# ledpower.net
KiCad netlist of a schematic drawn in EAGLE
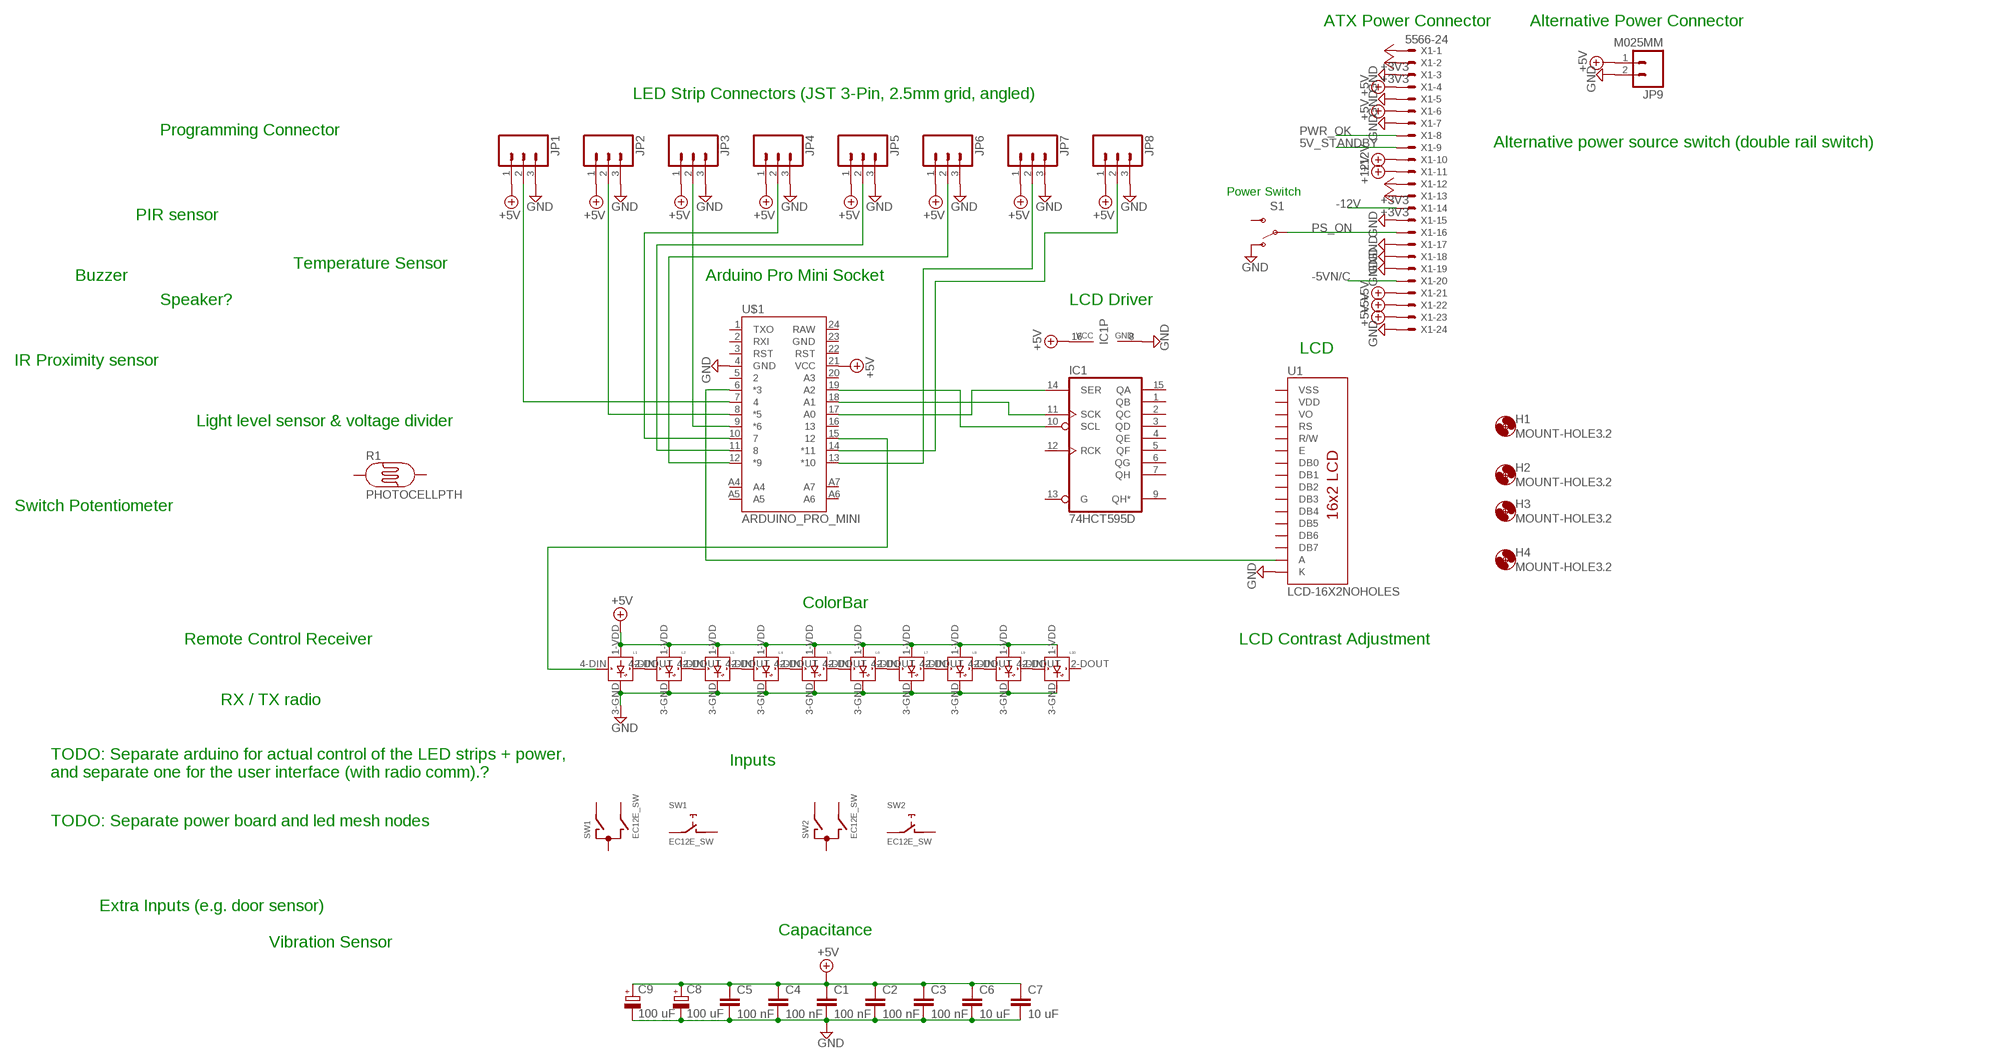
[diagram p0: schematic, sheet 1]

(export (version "E")
  (design (tool "Eeschema 10.0.6"))
  (components
    (comp (ref "C1")
      (value "100 nF")
      (footprint "eagle-import:C0805")
      (libsource (lib "eagle-import") (part "C-EUC0805"))
    )
    (comp (ref "C2")
      (value "100 nF")
      (footprint "eagle-import:C0805")
      (libsource (lib "eagle-import") (part "C-EUC0805"))
    )
    (comp (ref "C3")
      (value "100 nF")
      (footprint "eagle-import:C0805")
      (libsource (lib "eagle-import") (part "C-EUC0805"))
    )
    (comp (ref "C4")
      (value "100 nF")
      (footprint "eagle-import:C0805")
      (libsource (lib "eagle-import") (part "C-EUC0805"))
    )
    (comp (ref "C5")
      (value "100 nF")
      (footprint "eagle-import:C0805")
      (libsource (lib "eagle-import") (part "C-EUC0805"))
    )
    (comp (ref "C6")
      (value "10 uF")
      (footprint "eagle-import:C1206")
      (libsource (lib "eagle-import") (part "C-EUC1206"))
    )
    (comp (ref "C7")
      (value "10 uF")
      (footprint "eagle-import:C1206")
      (libsource (lib "eagle-import") (part "C-EUC1206"))
    )
    (comp (ref "C8")
      (value "100 uF")
      (footprint "eagle-import:E3,5-10")
      (libsource (lib "eagle-import") (part "CPOL-EUE3.5-10"))
    )
    (comp (ref "C9")
      (value "100 uF")
      (footprint "eagle-import:E3,5-10")
      (libsource (lib "eagle-import") (part "CPOL-EUE3.5-10"))
    )
    (comp (ref "H1")
      (value "MOUNT-HOLE3.2")
      (footprint "eagle-import:3,2")
      (libsource (lib "eagle-import") (part "MOUNT-HOLE3.2"))
    )
    (comp (ref "H2")
      (value "MOUNT-HOLE3.2")
      (footprint "eagle-import:3,2")
      (libsource (lib "eagle-import") (part "MOUNT-HOLE3.2"))
    )
    (comp (ref "H3")
      (value "MOUNT-HOLE3.2")
      (footprint "eagle-import:3,2")
      (libsource (lib "eagle-import") (part "MOUNT-HOLE3.2"))
    )
    (comp (ref "H4")
      (value "MOUNT-HOLE3.2")
      (footprint "eagle-import:3,2")
      (libsource (lib "eagle-import") (part "MOUNT-HOLE3.2"))
    )
    (comp (ref "IC1")
      (value "74HCT595D")
      (footprint "eagle-import:SO16")
      (libsource (lib "eagle-import") (part "74595DHCT"))
    )
    (comp (ref "JP1")
      (value "M03LONGPADS")
      (footprint "eagle-import:1X03_LONGPADS")
      (libsource (lib "eagle-import") (part "M03LONGPADS"))
    )
    (comp (ref "JP2")
      (value "M03LONGPADS")
      (footprint "eagle-import:1X03_LONGPADS")
      (libsource (lib "eagle-import") (part "M03LONGPADS"))
    )
    (comp (ref "JP3")
      (value "M03LONGPADS")
      (footprint "eagle-import:1X03_LONGPADS")
      (libsource (lib "eagle-import") (part "M03LONGPADS"))
    )
    (comp (ref "JP4")
      (value "M03LONGPADS")
      (footprint "eagle-import:1X03_LONGPADS")
      (libsource (lib "eagle-import") (part "M03LONGPADS"))
    )
    (comp (ref "JP5")
      (value "M03LONGPADS")
      (footprint "eagle-import:1X03_LONGPADS")
      (libsource (lib "eagle-import") (part "M03LONGPADS"))
    )
    (comp (ref "JP6")
      (value "M03LONGPADS")
      (footprint "eagle-import:1X03_LONGPADS")
      (libsource (lib "eagle-import") (part "M03LONGPADS"))
    )
    (comp (ref "JP7")
      (value "M03LONGPADS")
      (footprint "eagle-import:1X03_LONGPADS")
      (libsource (lib "eagle-import") (part "M03LONGPADS"))
    )
    (comp (ref "JP8")
      (value "M03LONGPADS")
      (footprint "eagle-import:1X03_LONGPADS")
      (libsource (lib "eagle-import") (part "M03LONGPADS"))
    )
    (comp (ref "JP9")
      (value "M025MM")
      (footprint "eagle-import:SCREWTERMINAL-5MM-2")
      (libsource (lib "eagle-import") (part "M025MM"))
    )
    (comp (ref "L1")
      (value "WS2812B")
      (footprint "eagle-import:WS2812B")
      (libsource (lib "eagle-import") (part "WS2812B"))
    )
    (comp (ref "L2")
      (value "WS2812B")
      (footprint "eagle-import:WS2812B")
      (libsource (lib "eagle-import") (part "WS2812B"))
    )
    (comp (ref "L3")
      (value "WS2812B")
      (footprint "eagle-import:WS2812B")
      (libsource (lib "eagle-import") (part "WS2812B"))
    )
    (comp (ref "L4")
      (value "WS2812B")
      (footprint "eagle-import:WS2812B")
      (libsource (lib "eagle-import") (part "WS2812B"))
    )
    (comp (ref "L5")
      (value "WS2812B")
      (footprint "eagle-import:WS2812B")
      (libsource (lib "eagle-import") (part "WS2812B"))
    )
    (comp (ref "L6")
      (value "WS2812B")
      (footprint "eagle-import:WS2812B")
      (libsource (lib "eagle-import") (part "WS2812B"))
    )
    (comp (ref "L7")
      (value "WS2812B")
      (footprint "eagle-import:WS2812B")
      (libsource (lib "eagle-import") (part "WS2812B"))
    )
    (comp (ref "L8")
      (value "WS2812B")
      (footprint "eagle-import:WS2812B")
      (libsource (lib "eagle-import") (part "WS2812B"))
    )
    (comp (ref "L9")
      (value "WS2812B")
      (footprint "eagle-import:WS2812B")
      (libsource (lib "eagle-import") (part "WS2812B"))
    )
    (comp (ref "L10")
      (value "WS2812B")
      (footprint "eagle-import:WS2812B")
      (libsource (lib "eagle-import") (part "WS2812B"))
    )
    (comp (ref "R1")
      (value "PHOTOCELLPTH")
      (footprint "eagle-import:PHOTOCELL")
      (libsource (lib "eagle-import") (part "PHOTOCELLPTH"))
    )
    (comp (ref "S1")
      (value "SWITCH-SPSTPTH")
      (footprint "eagle-import:SWITCH-SPDT")
      (libsource (lib "eagle-import") (part "SWITCH-SPSTPTH"))
    )
    (comp (ref "SW1")
      (value "EC12E_SW")
      (footprint "eagle-import:ALPS_EC12E_SW")
      (fields (field (name "MPN") "EC12E2424407"))
      (libsource (lib "eagle-import") (part "EC12E_SW"))
    )
    (comp (ref "SW2")
      (value "EC12E_SW")
      (footprint "eagle-import:ALPS_EC12E_SW")
      (fields (field (name "MPN") "EC12E2424407"))
      (libsource (lib "eagle-import") (part "EC12E_SW"))
    )
    (comp (ref "U$1")
      (value "ARDUINO_PRO_MINI")
      (footprint "eagle-import:ARDUINO_PRO_MINI")
      (libsource (lib "eagle-import") (part "ARDUINO_PRO_MINI"))
    )
    (comp (ref "U1")
      (value "LCD-16X2NOHOLES")
      (footprint "eagle-import:LCD-16X2_NOHOLES")
      (libsource (lib "eagle-import") (part "LCD-16X2NOHOLES"))
    )
    (comp (ref "X1")
      (value "5566-24")
      (footprint "eagle-import:5566-24")
      (libsource (lib "eagle-import") (part "5566-24"))
    )
  )
  (nets
    (net (code "1") (name "+3V3") (class "Default")
      (node (ref "X1") (pin "1") (pinfunction "S_1") (pintype "passive"))
      (node (ref "X1") (pin "12") (pinfunction "S_12") (pintype "passive"))
      (node (ref "X1") (pin "13") (pinfunction "S_13") (pintype "passive"))
      (node (ref "X1") (pin "2") (pinfunction "S_2") (pintype "passive"))
    )
    (net (code "2") (name "+5V") (class "Default")
      (node (ref "C1") (pin "1") (pinfunction "1_1") (pintype "passive"))
      (node (ref "C2") (pin "1") (pinfunction "1_1") (pintype "passive"))
      (node (ref "C3") (pin "1") (pinfunction "1_1") (pintype "passive"))
      (node (ref "C4") (pin "1") (pinfunction "1_1") (pintype "passive"))
      (node (ref "C5") (pin "1") (pinfunction "1_1") (pintype "passive"))
      (node (ref "C6") (pin "1") (pinfunction "1_1") (pintype "passive"))
      (node (ref "C7") (pin "1") (pinfunction "1_1") (pintype "passive"))
      (node (ref "C8") (pin "+") (pinfunction "+_+") (pintype "passive"))
      (node (ref "C9") (pin "+") (pinfunction "+_+") (pintype "passive"))
      (node (ref "IC1") (pin "16") (pinfunction "VCC_16") (pintype "power_in"))
      (node (ref "JP1") (pin "1") (pinfunction "1_1") (pintype "passive"))
      (node (ref "JP2") (pin "1") (pinfunction "1_1") (pintype "passive"))
      (node (ref "JP3") (pin "1") (pinfunction "1_1") (pintype "passive"))
      (node (ref "JP4") (pin "1") (pinfunction "1_1") (pintype "passive"))
      (node (ref "JP5") (pin "1") (pinfunction "1_1") (pintype "passive"))
      (node (ref "JP6") (pin "1") (pinfunction "1_1") (pintype "passive"))
      (node (ref "JP7") (pin "1") (pinfunction "1_1") (pintype "passive"))
      (node (ref "JP8") (pin "1") (pinfunction "1_1") (pintype "passive"))
      (node (ref "JP9") (pin "1") (pinfunction "1_1") (pintype "passive"))
      (node (ref "L1") (pin "1-VDD") (pinfunction "VDD_1-VDD") (pintype "bidirectional"))
      (node (ref "L10") (pin "1-VDD") (pinfunction "VDD_1-VDD") (pintype "bidirectional"))
      (node (ref "L2") (pin "1-VDD") (pinfunction "VDD_1-VDD") (pintype "bidirectional"))
      (node (ref "L3") (pin "1-VDD") (pinfunction "VDD_1-VDD") (pintype "bidirectional"))
      (node (ref "L4") (pin "1-VDD") (pinfunction "VDD_1-VDD") (pintype "bidirectional"))
      (node (ref "L5") (pin "1-VDD") (pinfunction "VDD_1-VDD") (pintype "bidirectional"))
      (node (ref "L6") (pin "1-VDD") (pinfunction "VDD_1-VDD") (pintype "bidirectional"))
      (node (ref "L7") (pin "1-VDD") (pinfunction "VDD_1-VDD") (pintype "bidirectional"))
      (node (ref "L8") (pin "1-VDD") (pinfunction "VDD_1-VDD") (pintype "bidirectional"))
      (node (ref "L9") (pin "1-VDD") (pinfunction "VDD_1-VDD") (pintype "bidirectional"))
      (node (ref "U$1") (pin "21") (pinfunction "VCC_21") (pintype "bidirectional"))
      (node (ref "X1") (pin "21") (pinfunction "S_21") (pintype "passive"))
      (node (ref "X1") (pin "22") (pinfunction "S_22") (pintype "passive"))
      (node (ref "X1") (pin "23") (pinfunction "S_23") (pintype "passive"))
      (node (ref "X1") (pin "4") (pinfunction "S_4") (pintype "passive"))
      (node (ref "X1") (pin "6") (pinfunction "S_6") (pintype "passive"))
    )
    (net (code "3") (name "+12V") (class "Default")
      (node (ref "X1") (pin "10") (pinfunction "S_10") (pintype "passive"))
      (node (ref "X1") (pin "11") (pinfunction "S_11") (pintype "passive"))
    )
    (net (code "4") (name "/-5VN{slash}C") (class "Default")
      (node (ref "X1") (pin "20") (pinfunction "S_20") (pintype "passive"))
    )
    (net (code "5") (name "/-12V") (class "Default")
      (node (ref "X1") (pin "14") (pinfunction "S_14") (pintype "passive"))
    )
    (net (code "6") (name "/5V_STANDBY") (class "Default")
      (node (ref "X1") (pin "9") (pinfunction "S_9") (pintype "passive"))
    )
    (net (code "7") (name "/PS_ON") (class "Default")
      (node (ref "S1") (pin "2") (pinfunction "P_2") (pintype "passive"))
      (node (ref "X1") (pin "16") (pinfunction "S_16") (pintype "passive"))
    )
    (net (code "8") (name "/PWR_OK") (class "Default")
      (node (ref "X1") (pin "8") (pinfunction "S_8") (pintype "passive"))
    )
    (net (code "9") (name "/VDD") (class "Default")
      (node (ref "U1") (pin "2") (pinfunction "VDD_2") (pintype "power_in"))
    )
    (net (code "10") (name "/VSS") (class "Default")
      (node (ref "U1") (pin "1") (pinfunction "VSS_1") (pintype "power_in"))
    )
    (net (code "11") (name "GND") (class "Default")
      (node (ref "C1") (pin "2") (pinfunction "2_2") (pintype "passive"))
      (node (ref "C2") (pin "2") (pinfunction "2_2") (pintype "passive"))
      (node (ref "C3") (pin "2") (pinfunction "2_2") (pintype "passive"))
      (node (ref "C4") (pin "2") (pinfunction "2_2") (pintype "passive"))
      (node (ref "C5") (pin "2") (pinfunction "2_2") (pintype "passive"))
      (node (ref "C6") (pin "2") (pinfunction "2_2") (pintype "passive"))
      (node (ref "C7") (pin "2") (pinfunction "2_2") (pintype "passive"))
      (node (ref "C8") (pin "-") (pinfunction "-_-") (pintype "passive"))
      (node (ref "C9") (pin "-") (pinfunction "-_-") (pintype "passive"))
      (node (ref "IC1") (pin "8") (pinfunction "GND_8") (pintype "power_in"))
      (node (ref "JP1") (pin "3") (pinfunction "3_3") (pintype "passive"))
      (node (ref "JP2") (pin "3") (pinfunction "3_3") (pintype "passive"))
      (node (ref "JP3") (pin "3") (pinfunction "3_3") (pintype "passive"))
      (node (ref "JP4") (pin "3") (pinfunction "3_3") (pintype "passive"))
      (node (ref "JP5") (pin "3") (pinfunction "3_3") (pintype "passive"))
      (node (ref "JP6") (pin "3") (pinfunction "3_3") (pintype "passive"))
      (node (ref "JP7") (pin "3") (pinfunction "3_3") (pintype "passive"))
      (node (ref "JP8") (pin "3") (pinfunction "3_3") (pintype "passive"))
      (node (ref "JP9") (pin "2") (pinfunction "2_2") (pintype "passive"))
      (node (ref "L1") (pin "3-GND") (pinfunction "GND_3-GND") (pintype "bidirectional"))
      (node (ref "L10") (pin "3-GND") (pinfunction "GND_3-GND") (pintype "bidirectional"))
      (node (ref "L2") (pin "3-GND") (pinfunction "GND_3-GND") (pintype "bidirectional"))
      (node (ref "L3") (pin "3-GND") (pinfunction "GND_3-GND") (pintype "bidirectional"))
      (node (ref "L4") (pin "3-GND") (pinfunction "GND_3-GND") (pintype "bidirectional"))
      (node (ref "L5") (pin "3-GND") (pinfunction "GND_3-GND") (pintype "bidirectional"))
      (node (ref "L6") (pin "3-GND") (pinfunction "GND_3-GND") (pintype "bidirectional"))
      (node (ref "L7") (pin "3-GND") (pinfunction "GND_3-GND") (pintype "bidirectional"))
      (node (ref "L8") (pin "3-GND") (pinfunction "GND_3-GND") (pintype "bidirectional"))
      (node (ref "L9") (pin "3-GND") (pinfunction "GND_3-GND") (pintype "bidirectional"))
      (node (ref "S1") (pin "1") (pinfunction "O_1") (pintype "passive"))
      (node (ref "U$1") (pin "4") (pinfunction "GND_4") (pintype "bidirectional"))
      (node (ref "U1") (pin "16") (pinfunction "K_16") (pintype "power_in"))
      (node (ref "X1") (pin "15") (pinfunction "S_15") (pintype "passive"))
      (node (ref "X1") (pin "17") (pinfunction "S_17") (pintype "passive"))
      (node (ref "X1") (pin "18") (pinfunction "S_18") (pintype "passive"))
      (node (ref "X1") (pin "19") (pinfunction "S_19") (pintype "passive"))
      (node (ref "X1") (pin "24") (pinfunction "S_24") (pintype "passive"))
      (node (ref "X1") (pin "3") (pinfunction "S_3") (pintype "passive"))
      (node (ref "X1") (pin "5") (pinfunction "S_5") (pintype "passive"))
      (node (ref "X1") (pin "7") (pinfunction "S_7") (pintype "passive"))
    )
    (net (code "12") (name "Net-(IC1A-SCK)") (class "Default")
      (node (ref "IC1") (pin "11") (pinfunction "SCK_11") (pintype "input"))
      (node (ref "U$1") (pin "18") (pinfunction "A1_18") (pintype "bidirectional"))
    )
    (net (code "13") (name "Net-(IC1A-SCL)") (class "Default")
      (node (ref "IC1") (pin "10") (pinfunction "SCL_10") (pintype "input"))
      (node (ref "U$1") (pin "19") (pinfunction "A2_19") (pintype "bidirectional"))
    )
    (net (code "14") (name "Net-(IC1A-SER)") (class "Default")
      (node (ref "IC1") (pin "14") (pinfunction "SER_14") (pintype "input"))
      (node (ref "U$1") (pin "17") (pinfunction "A0_17") (pintype "bidirectional"))
    )
    (net (code "15") (name "Net-(L1-DIN)") (class "Default")
      (node (ref "L1") (pin "4-DIN") (pinfunction "DIN_4-DIN") (pintype "input"))
      (node (ref "U$1") (pin "15") (pinfunction "12_15") (pintype "bidirectional"))
    )
    (net (code "16") (name "Net-(L1-DOUT)") (class "Default")
      (node (ref "L1") (pin "2-DOUT") (pinfunction "DOUT_2-DOUT") (pintype "output"))
      (node (ref "L2") (pin "4-DIN") (pinfunction "DIN_4-DIN") (pintype "input"))
    )
    (net (code "17") (name "Net-(L2-DOUT)") (class "Default")
      (node (ref "L2") (pin "2-DOUT") (pinfunction "DOUT_2-DOUT") (pintype "output"))
      (node (ref "L3") (pin "4-DIN") (pinfunction "DIN_4-DIN") (pintype "input"))
    )
    (net (code "18") (name "Net-(L3-DOUT)") (class "Default")
      (node (ref "L3") (pin "2-DOUT") (pinfunction "DOUT_2-DOUT") (pintype "output"))
      (node (ref "L4") (pin "4-DIN") (pinfunction "DIN_4-DIN") (pintype "input"))
    )
    (net (code "19") (name "Net-(L4-DOUT)") (class "Default")
      (node (ref "L4") (pin "2-DOUT") (pinfunction "DOUT_2-DOUT") (pintype "output"))
      (node (ref "L5") (pin "4-DIN") (pinfunction "DIN_4-DIN") (pintype "input"))
    )
    (net (code "20") (name "Net-(L5-DOUT)") (class "Default")
      (node (ref "L5") (pin "2-DOUT") (pinfunction "DOUT_2-DOUT") (pintype "output"))
      (node (ref "L6") (pin "4-DIN") (pinfunction "DIN_4-DIN") (pintype "input"))
    )
    (net (code "21") (name "Net-(L6-DOUT)") (class "Default")
      (node (ref "L6") (pin "2-DOUT") (pinfunction "DOUT_2-DOUT") (pintype "output"))
      (node (ref "L7") (pin "4-DIN") (pinfunction "DIN_4-DIN") (pintype "input"))
    )
    (net (code "22") (name "Net-(L7-DOUT)") (class "Default")
      (node (ref "L7") (pin "2-DOUT") (pinfunction "DOUT_2-DOUT") (pintype "output"))
      (node (ref "L8") (pin "4-DIN") (pinfunction "DIN_4-DIN") (pintype "input"))
    )
    (net (code "23") (name "Net-(L8-DOUT)") (class "Default")
      (node (ref "L8") (pin "2-DOUT") (pinfunction "DOUT_2-DOUT") (pintype "output"))
      (node (ref "L9") (pin "4-DIN") (pinfunction "DIN_4-DIN") (pintype "input"))
    )
    (net (code "24") (name "Net-(L10-DIN)") (class "Default")
      (node (ref "L10") (pin "4-DIN") (pinfunction "DIN_4-DIN") (pintype "input"))
      (node (ref "L9") (pin "2-DOUT") (pinfunction "DOUT_2-DOUT") (pintype "output"))
    )
    (net (code "25") (name "Net-(U$1-*3)") (class "Default")
      (node (ref "U$1") (pin "6") (pinfunction "*3_6") (pintype "bidirectional"))
      (node (ref "U1") (pin "15") (pinfunction "A_15") (pintype "power_in"))
    )
    (net (code "26") (name "Net-(U$1-*5)") (class "Default")
      (node (ref "JP2") (pin "2") (pinfunction "2_2") (pintype "passive"))
      (node (ref "U$1") (pin "8") (pinfunction "*5_8") (pintype "bidirectional"))
    )
    (net (code "27") (name "Net-(U$1-*6)") (class "Default")
      (node (ref "JP3") (pin "2") (pinfunction "2_2") (pintype "passive"))
      (node (ref "U$1") (pin "9") (pinfunction "*6_9") (pintype "bidirectional"))
    )
    (net (code "28") (name "Net-(U$1-*9)") (class "Default")
      (node (ref "JP6") (pin "2") (pinfunction "2_2") (pintype "passive"))
      (node (ref "U$1") (pin "12") (pinfunction "*9_12") (pintype "bidirectional"))
    )
    (net (code "29") (name "Net-(U$1-*10)") (class "Default")
      (node (ref "JP7") (pin "2") (pinfunction "2_2") (pintype "passive"))
      (node (ref "U$1") (pin "13") (pinfunction "*10_13") (pintype "bidirectional"))
    )
    (net (code "30") (name "Net-(U$1-*11)") (class "Default")
      (node (ref "JP8") (pin "2") (pinfunction "2_2") (pintype "passive"))
      (node (ref "U$1") (pin "14") (pinfunction "*11_14") (pintype "bidirectional"))
    )
    (net (code "31") (name "Net-(U$1-4)") (class "Default")
      (node (ref "JP1") (pin "2") (pinfunction "2_2") (pintype "passive"))
      (node (ref "U$1") (pin "7") (pinfunction "4_7") (pintype "bidirectional"))
    )
    (net (code "32") (name "Net-(U$1-7)") (class "Default")
      (node (ref "JP4") (pin "2") (pinfunction "2_2") (pintype "passive"))
      (node (ref "U$1") (pin "10") (pinfunction "7_10") (pintype "bidirectional"))
    )
    (net (code "33") (name "Net-(U$1-8)") (class "Default")
      (node (ref "JP5") (pin "2") (pinfunction "2_2") (pintype "passive"))
      (node (ref "U$1") (pin "11") (pinfunction "8_11") (pintype "bidirectional"))
    )
    (net (code "34") (name "unconnected-(IC1A-G-Pad13)") (class "Default")
      (node (ref "IC1") (pin "13") (pinfunction "G_13") (pintype "input"))
    )
    (net (code "35") (name "unconnected-(IC1A-QA-Pad15)") (class "Default")
      (node (ref "IC1") (pin "15") (pinfunction "QA_15") (pintype "tri_state"))
    )
    (net (code "36") (name "unconnected-(IC1A-QB-Pad1)") (class "Default")
      (node (ref "IC1") (pin "1") (pinfunction "QB_1") (pintype "tri_state"))
    )
    (net (code "37") (name "unconnected-(IC1A-QC-Pad2)") (class "Default")
      (node (ref "IC1") (pin "2") (pinfunction "QC_2") (pintype "tri_state"))
    )
    (net (code "38") (name "unconnected-(IC1A-QD-Pad3)") (class "Default")
      (node (ref "IC1") (pin "3") (pinfunction "QD_3") (pintype "tri_state"))
    )
    (net (code "39") (name "unconnected-(IC1A-QE-Pad4)") (class "Default")
      (node (ref "IC1") (pin "4") (pinfunction "QE_4") (pintype "tri_state"))
    )
    (net (code "40") (name "unconnected-(IC1A-QF-Pad5)") (class "Default")
      (node (ref "IC1") (pin "5") (pinfunction "QF_5") (pintype "tri_state"))
    )
    (net (code "41") (name "unconnected-(IC1A-QG-Pad6)") (class "Default")
      (node (ref "IC1") (pin "6") (pinfunction "QG_6") (pintype "tri_state"))
    )
    (net (code "42") (name "unconnected-(IC1A-QH*-Pad9)") (class "Default")
      (node (ref "IC1") (pin "9") (pinfunction "QH*_9") (pintype "tri_state"))
    )
    (net (code "43") (name "unconnected-(IC1A-QH-Pad7)") (class "Default")
      (node (ref "IC1") (pin "7") (pinfunction "QH_7") (pintype "tri_state"))
    )
    (net (code "44") (name "unconnected-(IC1A-RCK-Pad12)") (class "Default")
      (node (ref "IC1") (pin "12") (pinfunction "RCK_12") (pintype "input"))
    )
    (net (code "45") (name "unconnected-(L10-DOUT-Pad2-DOUT)") (class "Default")
      (node (ref "L10") (pin "2-DOUT") (pinfunction "DOUT_2-DOUT") (pintype "output"))
    )
    (net (code "46") (name "unconnected-(R1-P$1-Pad1)") (class "Default")
      (node (ref "R1") (pin "1") (pinfunction "P$1_1") (pintype "bidirectional"))
    )
    (net (code "47") (name "unconnected-(R1-P$2-Pad2)") (class "Default")
      (node (ref "R1") (pin "2") (pinfunction "P$2_2") (pintype "bidirectional"))
    )
    (net (code "48") (name "unconnected-(S1-S-Pad3)") (class "Default")
      (node (ref "S1") (pin "3") (pinfunction "S_3") (pintype "passive"))
    )
    (net (code "49") (name "unconnected-(SW1-PadA)") (class "Default")
      (node (ref "SW1") (pin "A") (pinfunction "A_A") (pintype "passive"))
    )
    (net (code "50") (name "unconnected-(SW1-PadB)") (class "Default")
      (node (ref "SW1") (pin "B") (pinfunction "B_B") (pintype "passive"))
    )
    (net (code "51") (name "unconnected-(SW1-PadC)") (class "Default")
      (node (ref "SW1") (pin "C") (pinfunction "C_C") (pintype "passive"))
    )
    (net (code "52") (name "unconnected-(SW1B-1-PadD)") (class "Default")
      (node (ref "SW1") (pin "D") (pinfunction "1_D") (pintype "passive"))
    )
    (net (code "53") (name "unconnected-(SW1B-2-PadE)") (class "Default")
      (node (ref "SW1") (pin "E") (pinfunction "2_E") (pintype "passive"))
    )
    (net (code "54") (name "unconnected-(SW2-PadA)") (class "Default")
      (node (ref "SW2") (pin "A") (pinfunction "A_A") (pintype "passive"))
    )
    (net (code "55") (name "unconnected-(SW2-PadB)") (class "Default")
      (node (ref "SW2") (pin "B") (pinfunction "B_B") (pintype "passive"))
    )
    (net (code "56") (name "unconnected-(SW2-PadC)") (class "Default")
      (node (ref "SW2") (pin "C") (pinfunction "C_C") (pintype "passive"))
    )
    (net (code "57") (name "unconnected-(SW2B-1-PadD)") (class "Default")
      (node (ref "SW2") (pin "D") (pinfunction "1_D") (pintype "passive"))
    )
    (net (code "58") (name "unconnected-(SW2B-2-PadE)") (class "Default")
      (node (ref "SW2") (pin "E") (pinfunction "2_E") (pintype "passive"))
    )
    (net (code "59") (name "unconnected-(U$1-2-Pad5)") (class "Default")
      (node (ref "U$1") (pin "5") (pinfunction "2_5") (pintype "bidirectional"))
    )
    (net (code "60") (name "unconnected-(U$1-13-Pad16)") (class "Default")
      (node (ref "U$1") (pin "16") (pinfunction "13_16") (pintype "bidirectional"))
    )
    (net (code "61") (name "unconnected-(U$1-A3-Pad20)") (class "Default")
      (node (ref "U$1") (pin "20") (pinfunction "A3_20") (pintype "bidirectional"))
    )
    (net (code "62") (name "unconnected-(U$1-GND-Pad23)") (class "Default")
      (node (ref "U$1") (pin "23") (pinfunction "GND_23") (pintype "bidirectional"))
    )
    (net (code "63") (name "unconnected-(U$1-PadA4)") (class "Default")
      (node (ref "U$1") (pin "A4") (pinfunction "A4_A4") (pintype "bidirectional"))
    )
    (net (code "64") (name "unconnected-(U$1-PadA5)") (class "Default")
      (node (ref "U$1") (pin "A5") (pinfunction "A5_A5") (pintype "bidirectional"))
    )
    (net (code "65") (name "unconnected-(U$1-PadA6)") (class "Default")
      (node (ref "U$1") (pin "A6") (pinfunction "A6_A6") (pintype "bidirectional"))
    )
    (net (code "66") (name "unconnected-(U$1-PadA7)") (class "Default")
      (node (ref "U$1") (pin "A7") (pinfunction "A7_A7") (pintype "bidirectional"))
    )
    (net (code "67") (name "unconnected-(U$1-RAW-Pad24)") (class "Default")
      (node (ref "U$1") (pin "24") (pinfunction "RAW_24") (pintype "bidirectional"))
    )
    (net (code "68") (name "unconnected-(U$1-RST-Pad3)") (class "Default")
      (node (ref "U$1") (pin "3") (pinfunction "RST_3") (pintype "bidirectional"))
    )
    (net (code "69") (name "unconnected-(U$1-RST-Pad22)") (class "Default")
      (node (ref "U$1") (pin "22") (pinfunction "RST_22") (pintype "bidirectional"))
    )
    (net (code "70") (name "unconnected-(U$1-RXI-Pad2)") (class "Default")
      (node (ref "U$1") (pin "2") (pinfunction "RXI_2") (pintype "bidirectional"))
    )
    (net (code "71") (name "unconnected-(U$1-TXO-Pad1)") (class "Default")
      (node (ref "U$1") (pin "1") (pinfunction "TXO_1") (pintype "bidirectional"))
    )
    (net (code "72") (name "unconnected-(U1-DB0-Pad7)") (class "Default")
      (node (ref "U1") (pin "7") (pinfunction "DB0_7") (pintype "bidirectional"))
    )
    (net (code "73") (name "unconnected-(U1-DB1-Pad8)") (class "Default")
      (node (ref "U1") (pin "8") (pinfunction "DB1_8") (pintype "bidirectional"))
    )
    (net (code "74") (name "unconnected-(U1-DB2-Pad9)") (class "Default")
      (node (ref "U1") (pin "9") (pinfunction "DB2_9") (pintype "bidirectional"))
    )
    (net (code "75") (name "unconnected-(U1-DB3-Pad10)") (class "Default")
      (node (ref "U1") (pin "10") (pinfunction "DB3_10") (pintype "bidirectional"))
    )
    (net (code "76") (name "unconnected-(U1-DB4-Pad11)") (class "Default")
      (node (ref "U1") (pin "11") (pinfunction "DB4_11") (pintype "bidirectional"))
    )
    (net (code "77") (name "unconnected-(U1-DB5-Pad12)") (class "Default")
      (node (ref "U1") (pin "12") (pinfunction "DB5_12") (pintype "bidirectional"))
    )
    (net (code "78") (name "unconnected-(U1-DB6-Pad13)") (class "Default")
      (node (ref "U1") (pin "13") (pinfunction "DB6_13") (pintype "bidirectional"))
    )
    (net (code "79") (name "unconnected-(U1-DB7-Pad14)") (class "Default")
      (node (ref "U1") (pin "14") (pinfunction "DB7_14") (pintype "bidirectional"))
    )
    (net (code "80") (name "unconnected-(U1-E-Pad6)") (class "Default")
      (node (ref "U1") (pin "6") (pinfunction "E_6") (pintype "input"))
    )
    (net (code "81") (name "unconnected-(U1-RS-Pad4)") (class "Default")
      (node (ref "U1") (pin "4") (pinfunction "RS_4") (pintype "input"))
    )
    (net (code "82") (name "unconnected-(U1-R{slash}W-Pad5)") (class "Default")
      (node (ref "U1") (pin "5") (pinfunction "R/W_5") (pintype "input"))
    )
    (net (code "83") (name "unconnected-(U1-VO-Pad3)") (class "Default")
      (node (ref "U1") (pin "3") (pinfunction "VO_3") (pintype "bidirectional"))
    )
  )
)
